# 5-2_fpga_config.net
KiCad netlist of a schematic drawn in Altium Designer
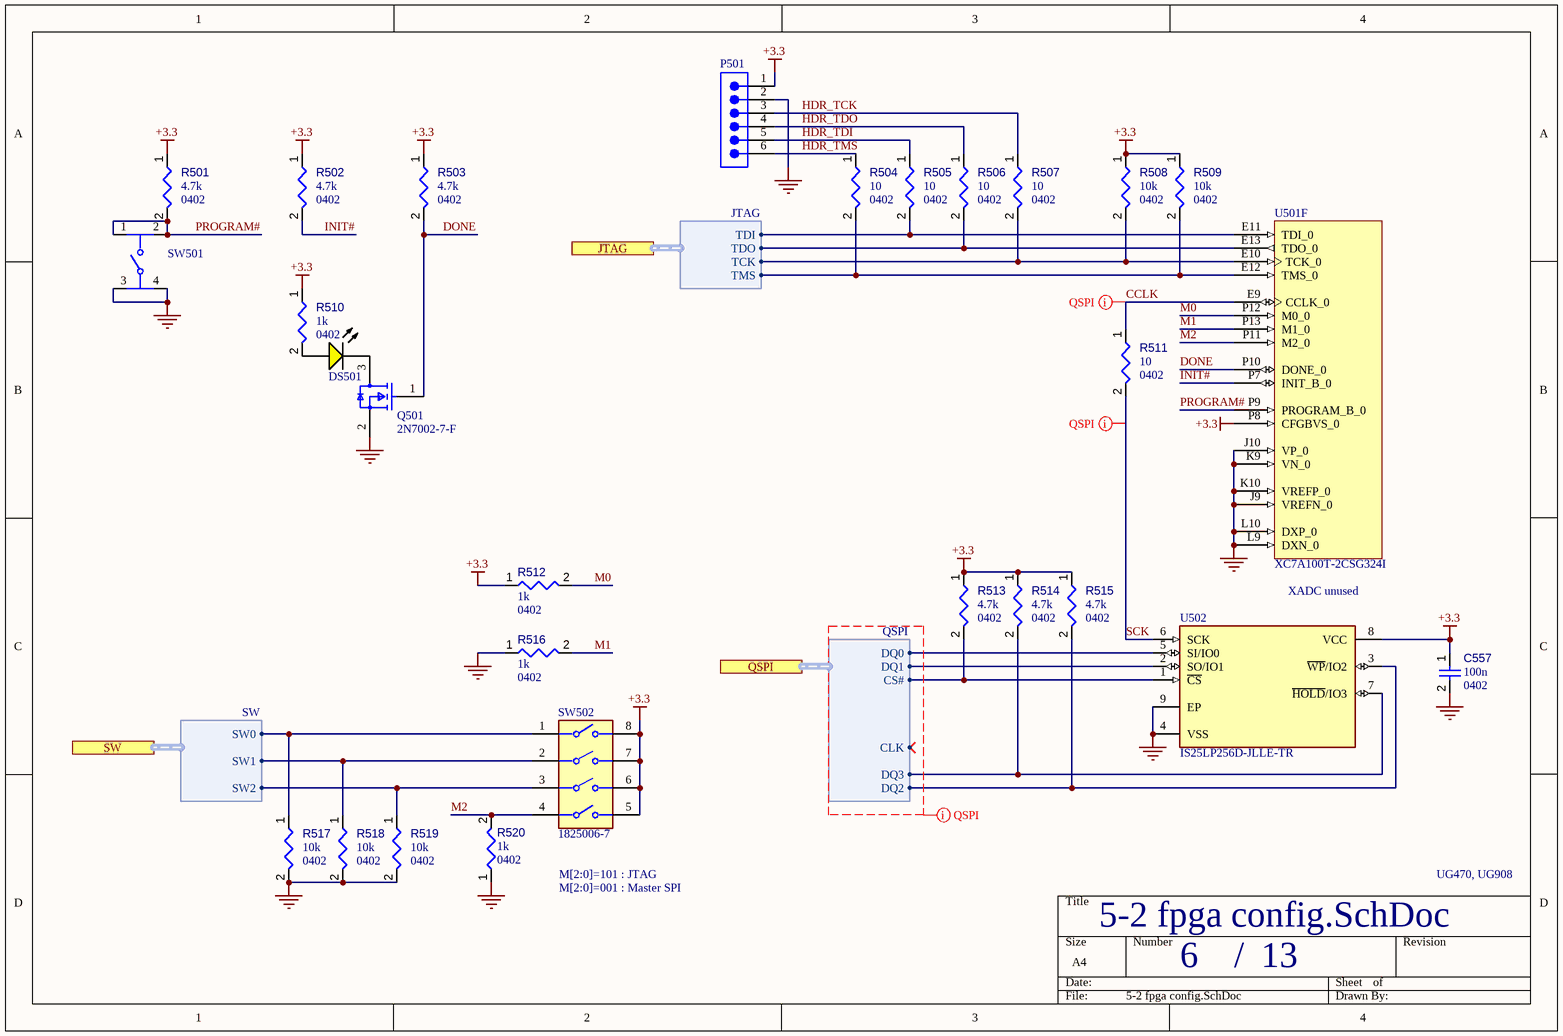
[diagram p0: 5-2 fpga config.SchDoc]

(export (version "E")
  (design (tool "Eeschema 10.0.6"))
  (components
    (comp (ref "C557")
      (value "100n")
      (footprint "CAPC0402(1005)60_L")
      (description "Capacitor")
      (fields (field (name "CASE/PACKAGE") "0402") (field (name "Comment") "Capacitors,0402,100n,16"))
      (libsource (lib "UBC Uncrewed Aircraft Systems") (part "CAP-NP-2"))
    )
    (comp (ref "DS501")
      (value "SML-LX0603YW-TR")
      (footprint "LUMX-SML-LX0603_V")
      (fields (field (name "MANUFACTURER") "Lumex"))
      (libsource (lib "Altium Content Vault") (part "LED-YELLOW-AK-2"))
    )
    (comp (ref "P501")
      (value "TSW-106-07-F-S")
      (footprint "SMTC-TSW-106-07-X-S")
      (description "0.025\" SQ Post Header, Through-hole, Vertical, -55 to 125 degC, 2.54 mm Pitch, 6-Pin, Male, RoHS")
      (fields (field (name "MANUFACTURER") "Samtec"))
      (libsource (lib "Altium Content Vault") (part "SMTC-TSW-106-X-X-S-X"))
    )
    (comp (ref "Q501")
      (value "2N7002-7-F")
      (footprint "FP-SOT23-MFG")
      (description "MOSFET N-CH 60V 115MA SOT23-3")
      (fields (field (name "VOLTAGE") "60V"))
      (libsource (lib "Altium Content Vault") (part "3b9c635fedb024a5347a57b145af9cc"))
    )
    (comp (ref "R501")
      (value "4.7k")
      (footprint "RESC0402(1005)_L")
      (description "Resistor")
      (fields (field (name "CASE/PACKAGE") "0402") (field (name "Comment") "Resistors,0402,4.7k"))
      (libsource (lib "UBC Uncrewed Aircraft Systems") (part "RES-2"))
    )
    (comp (ref "R502")
      (value "4.7k")
      (footprint "RESC0402(1005)_L")
      (description "Resistor")
      (fields (field (name "CASE/PACKAGE") "0402") (field (name "Comment") "Resistors,0402,4.7k"))
      (libsource (lib "UBC Uncrewed Aircraft Systems") (part "RES-2"))
    )
    (comp (ref "R503")
      (value "4.7k")
      (footprint "RESC0402(1005)_L")
      (description "Resistor")
      (fields (field (name "CASE/PACKAGE") "0402") (field (name "Comment") "Resistors,0402,4.7k"))
      (libsource (lib "UBC Uncrewed Aircraft Systems") (part "RES-2"))
    )
    (comp (ref "R504")
      (value "10")
      (footprint "RESC0402(1005)_L")
      (description "Resistor")
      (fields (field (name "CASE/PACKAGE") "0402") (field (name "Comment") "Resistors,0402,10"))
      (libsource (lib "UBC Uncrewed Aircraft Systems") (part "RES-2"))
    )
    (comp (ref "R505")
      (value "10")
      (footprint "RESC0402(1005)_L")
      (description "Resistor")
      (fields (field (name "CASE/PACKAGE") "0402") (field (name "Comment") "Resistors,0402,10"))
      (libsource (lib "UBC Uncrewed Aircraft Systems") (part "RES-2"))
    )
    (comp (ref "R506")
      (value "10")
      (footprint "RESC0402(1005)_L")
      (description "Resistor")
      (fields (field (name "CASE/PACKAGE") "0402") (field (name "Comment") "Resistors,0402,10"))
      (libsource (lib "UBC Uncrewed Aircraft Systems") (part "RES-2"))
    )
    (comp (ref "R507")
      (value "10")
      (footprint "RESC0402(1005)_L")
      (description "Resistor")
      (fields (field (name "CASE/PACKAGE") "0402") (field (name "Comment") "Resistors,0402,10"))
      (libsource (lib "UBC Uncrewed Aircraft Systems") (part "RES-2"))
    )
    (comp (ref "R508")
      (value "10k")
      (footprint "RESC0402(1005)_L")
      (description "Resistor")
      (fields (field (name "CASE/PACKAGE") "0402") (field (name "Comment") "Resistors,0402,10k"))
      (libsource (lib "UBC Uncrewed Aircraft Systems") (part "RES-2"))
    )
    (comp (ref "R509")
      (value "10k")
      (footprint "RESC0402(1005)_L")
      (description "Resistor")
      (fields (field (name "CASE/PACKAGE") "0402") (field (name "Comment") "Resistors,0402,10k"))
      (libsource (lib "UBC Uncrewed Aircraft Systems") (part "RES-2"))
    )
    (comp (ref "R510")
      (value "1k")
      (footprint "RESC0402(1005)_L")
      (description "Resistor")
      (fields (field (name "CASE/PACKAGE") "0402") (field (name "Comment") "Resistors,0402,1k"))
      (libsource (lib "UBC Uncrewed Aircraft Systems") (part "RES-2"))
    )
    (comp (ref "R511")
      (value "10")
      (footprint "RESC0402(1005)_L")
      (description "Resistor")
      (fields (field (name "CASE/PACKAGE") "0402") (field (name "Comment") "Resistors,0402,10"))
      (libsource (lib "UBC Uncrewed Aircraft Systems") (part "RES-2"))
    )
    (comp (ref "R512")
      (value "1k")
      (footprint "RESC0402(1005)_L")
      (description "Resistor")
      (fields (field (name "CASE/PACKAGE") "0402") (field (name "Comment") "Resistors,0402,1k"))
      (libsource (lib "UBC Uncrewed Aircraft Systems") (part "RES-2"))
    )
    (comp (ref "R513")
      (value "4.7k")
      (footprint "RESC0402(1005)_L")
      (description "Resistor")
      (fields (field (name "CASE/PACKAGE") "0402") (field (name "Comment") "Resistors,0402,4.7k"))
      (libsource (lib "UBC Uncrewed Aircraft Systems") (part "RES-2"))
    )
    (comp (ref "R514")
      (value "4.7k")
      (footprint "RESC0402(1005)_L")
      (description "Resistor")
      (fields (field (name "CASE/PACKAGE") "0402") (field (name "Comment") "Resistors,0402,4.7k"))
      (libsource (lib "UBC Uncrewed Aircraft Systems") (part "RES-2"))
    )
    (comp (ref "R515")
      (value "4.7k")
      (footprint "RESC0402(1005)_L")
      (description "Resistor")
      (fields (field (name "CASE/PACKAGE") "0402") (field (name "Comment") "Resistors,0402,4.7k"))
      (libsource (lib "UBC Uncrewed Aircraft Systems") (part "RES-2"))
    )
    (comp (ref "R516")
      (value "1k")
      (footprint "RESC0402(1005)_L")
      (description "Resistor")
      (fields (field (name "CASE/PACKAGE") "0402") (field (name "Comment") "Resistors,0402,1k"))
      (libsource (lib "UBC Uncrewed Aircraft Systems") (part "RES-2"))
    )
    (comp (ref "R517")
      (value "10k")
      (footprint "RESC0402(1005)_L")
      (description "Resistor")
      (fields (field (name "CASE/PACKAGE") "0402") (field (name "Comment") "Resistors,0402,10k"))
      (libsource (lib "UBC Uncrewed Aircraft Systems") (part "RES-2"))
    )
    (comp (ref "R518")
      (value "10k")
      (footprint "RESC0402(1005)_L")
      (description "Resistor")
      (fields (field (name "CASE/PACKAGE") "0402") (field (name "Comment") "Resistors,0402,10k"))
      (libsource (lib "UBC Uncrewed Aircraft Systems") (part "RES-2"))
    )
    (comp (ref "R519")
      (value "10k")
      (footprint "RESC0402(1005)_L")
      (description "Resistor")
      (fields (field (name "CASE/PACKAGE") "0402") (field (name "Comment") "Resistors,0402,10k"))
      (libsource (lib "UBC Uncrewed Aircraft Systems") (part "RES-2"))
    )
    (comp (ref "R520")
      (value "1k")
      (footprint "RESC0402(1005)_L")
      (description "Resistor")
      (fields (field (name "CASE/PACKAGE") "0402") (field (name "Comment") "Resistors,0402,1k"))
      (libsource (lib "UBC Uncrewed Aircraft Systems") (part "RES-2"))
    )
    (comp (ref "SW501")
      (value "PTS810SJM250SMTRLFS")
      (footprint "FP-PTS810SJM250SMTRLFS-MFG")
      (description "SWITCH TACTILE SPST-NO 0.05A 16V")
      (libsource (lib "Altium Content Vault") (part "1adf0dd01260c80cf25a44bfd6b99ba"))
    )
    (comp (ref "SW502")
      (value "1825006-7")
      (footprint "FP-1825006-7-MFG")
      (description "SWITCH SLIDE DIP SPST 25MA 24V")
      (libsource (lib "Altium Content Vault") (part "68455c0d9ce67c59adf7292e62b4e22"))
    )
    (comp (ref "U501")
      (value "XC7A100T-2CSG324I")
      (footprint "CSG324")
      (description "Artix-7 FPGA, 210 User I/Os, 0 GTP, 324-Ball BGA, Speed Grade 2, Extended Grade, Pb-Free")
      (fields (field (name "MANUFACTURER") "Xilinx") (field (name "GENERIC PART NUMBER") "XC7A100T"))
      (libsource (lib "Altium Content Vault") (part "XNLX-XC7A100T-XNLX-CSG324"))
    )
    (comp (ref "U502")
      (value "IS25LP256D-JLLE-TR")
      (footprint "FP-PG-WSON-8-IPC_A")
      (description "S25FL256SAGNFV000 128 Mbit (16 Mbyte)/256 Mbit (32 Mbyte) 3.0V SPI Flash Memory")
      (libsource (lib "Altium Content Vault") (part "248553bbdf33aab5cdb7ae52e9f9a5b"))
    )
  )
  (nets
    (net (code "4") (name "+3.3") (class "Default")
      (node (ref "C557") (pin "1") (pinfunction "1_1") (pintype "passive"))
      (node (ref "P501") (pin "1") (pinfunction "1_1") (pintype "passive"))
      (node (ref "R501") (pin "1") (pinfunction "1_1") (pintype "passive"))
      (node (ref "R502") (pin "1") (pinfunction "1_1") (pintype "passive"))
      (node (ref "R503") (pin "1") (pinfunction "1_1") (pintype "passive"))
      (node (ref "R508") (pin "1") (pinfunction "1_1") (pintype "passive"))
      (node (ref "R509") (pin "1") (pinfunction "1_1") (pintype "passive"))
      (node (ref "R510") (pin "1") (pinfunction "1_1") (pintype "passive"))
      (node (ref "R512") (pin "1") (pinfunction "1_1") (pintype "passive"))
      (node (ref "R513") (pin "1") (pinfunction "1_1") (pintype "passive"))
      (node (ref "R514") (pin "1") (pinfunction "1_1") (pintype "passive"))
      (node (ref "R515") (pin "1") (pinfunction "1_1") (pintype "passive"))
      (node (ref "SW502") (pin "5") (pinfunction "5_5") (pintype "passive"))
      (node (ref "SW502") (pin "6") (pinfunction "6_6") (pintype "passive"))
      (node (ref "SW502") (pin "7") (pinfunction "7_7") (pintype "passive"))
      (node (ref "SW502") (pin "8") (pinfunction "8_8") (pintype "passive"))
      (node (ref "U501") (pin "P8") (pinfunction "CFGBVS_0_P8") (pintype "input"))
      (node (ref "U502") (pin "8") (pinfunction "VCC_8") (pintype "power_in"))
    )
    (net (code "5") (name "/CCLK") (class "Default")
      (node (ref "R511") (pin "1") (pinfunction "1_1") (pintype "passive"))
      (node (ref "U501") (pin "E9") (pinfunction "CCLK_0_E9") (pintype "bidirectional"))
    )
    (net (code "6") (name "/CS#") (class "Default")
      (node (ref "R513") (pin "2") (pinfunction "2_2") (pintype "passive"))
      (node (ref "U502") (pin "1") (pinfunction "~{CS}_1") (pintype "input"))
    )
    (net (code "7") (name "/DONE") (class "Default")
      (node (ref "Q501") (pin "1") (pinfunction "G_1") (pintype "passive"))
      (node (ref "R503") (pin "2") (pinfunction "2_2") (pintype "passive"))
      (node (ref "U501") (pin "P10") (pinfunction "DONE_0_P10") (pintype "bidirectional"))
    )
    (net (code "8") (name "/DQ0") (class "Default")
      (node (ref "U502") (pin "5") (pinfunction "SI/IO0_5") (pintype "bidirectional"))
    )
    (net (code "9") (name "/DQ1") (class "Default")
      (node (ref "U502") (pin "2") (pinfunction "SO/IO1_2") (pintype "bidirectional"))
    )
    (net (code "10") (name "/DQ2") (class "Default")
      (node (ref "R515") (pin "2") (pinfunction "2_2") (pintype "passive"))
      (node (ref "U502") (pin "3") (pinfunction "~{WP}/IO2_3") (pintype "bidirectional"))
    )
    (net (code "11") (name "/DQ3") (class "Default")
      (node (ref "R514") (pin "2") (pinfunction "2_2") (pintype "passive"))
      (node (ref "U502") (pin "7") (pinfunction "~{HOLD}/IO3_7") (pintype "bidirectional"))
    )
    (net (code "12") (name "/HDR_TCK") (class "Default")
      (node (ref "P501") (pin "3") (pinfunction "3_3") (pintype "passive"))
      (node (ref "R507") (pin "1") (pinfunction "1_1") (pintype "passive"))
    )
    (net (code "13") (name "/HDR_TDI") (class "Default")
      (node (ref "P501") (pin "5") (pinfunction "5_5") (pintype "passive"))
      (node (ref "R505") (pin "1") (pinfunction "1_1") (pintype "passive"))
    )
    (net (code "14") (name "/HDR_TDO") (class "Default")
      (node (ref "P501") (pin "4") (pinfunction "4_4") (pintype "passive"))
      (node (ref "R506") (pin "1") (pinfunction "1_1") (pintype "passive"))
    )
    (net (code "15") (name "/HDR_TMS") (class "Default")
      (node (ref "P501") (pin "6") (pinfunction "6_6") (pintype "passive"))
      (node (ref "R504") (pin "1") (pinfunction "1_1") (pintype "passive"))
    )
    (net (code "16") (name "/INIT#") (class "Default")
      (node (ref "R502") (pin "2") (pinfunction "2_2") (pintype "passive"))
      (node (ref "U501") (pin "P7") (pinfunction "INIT_B_0_P7") (pintype "bidirectional"))
    )
    (net (code "17") (name "/M0") (class "Default")
      (node (ref "R512") (pin "2") (pinfunction "2_2") (pintype "passive"))
      (node (ref "U501") (pin "P12") (pinfunction "M0_0_P12") (pintype "input"))
    )
    (net (code "18") (name "/M1") (class "Default")
      (node (ref "R516") (pin "2") (pinfunction "2_2") (pintype "passive"))
      (node (ref "U501") (pin "P13") (pinfunction "M1_0_P13") (pintype "input"))
    )
    (net (code "19") (name "/M2") (class "Default")
      (node (ref "R520") (pin "2") (pinfunction "2_2") (pintype "passive"))
      (node (ref "SW502") (pin "4") (pinfunction "4_4") (pintype "passive"))
      (node (ref "U501") (pin "P11") (pinfunction "M2_0_P11") (pintype "input"))
    )
    (net (code "20") (name "/PROGRAM#") (class "Default")
      (node (ref "R501") (pin "2") (pinfunction "2_2") (pintype "passive"))
      (node (ref "SW501") (pin "1") (pinfunction "1_1") (pintype "passive"))
      (node (ref "SW501") (pin "2") (pinfunction "2_2") (pintype "passive"))
      (node (ref "U501") (pin "P9") (pinfunction "PROGRAM_B_0_P9") (pintype "input"))
    )
    (net (code "21") (name "/SCK") (class "Default")
      (node (ref "R511") (pin "2") (pinfunction "2_2") (pintype "passive"))
      (node (ref "U502") (pin "6") (pinfunction "SCK_6") (pintype "input"))
    )
    (net (code "22") (name "/SW0") (class "Default")
      (node (ref "R517") (pin "1") (pinfunction "1_1") (pintype "passive"))
      (node (ref "SW502") (pin "1") (pinfunction "1_1") (pintype "passive"))
    )
    (net (code "23") (name "/SW1") (class "Default")
      (node (ref "R518") (pin "1") (pinfunction "1_1") (pintype "passive"))
      (node (ref "SW502") (pin "2") (pinfunction "2_2") (pintype "passive"))
    )
    (net (code "24") (name "/SW2") (class "Default")
      (node (ref "R519") (pin "1") (pinfunction "1_1") (pintype "passive"))
      (node (ref "SW502") (pin "3") (pinfunction "3_3") (pintype "passive"))
    )
    (net (code "25") (name "/TCK") (class "Default")
      (node (ref "R507") (pin "2") (pinfunction "2_2") (pintype "passive"))
      (node (ref "R508") (pin "2") (pinfunction "2_2") (pintype "passive"))
      (node (ref "U501") (pin "E10") (pinfunction "TCK_0_E10") (pintype "input"))
    )
    (net (code "26") (name "/TDI") (class "Default")
      (node (ref "R505") (pin "2") (pinfunction "2_2") (pintype "passive"))
      (node (ref "U501") (pin "E11") (pinfunction "TDI_0_E11") (pintype "input"))
    )
    (net (code "27") (name "/TDO") (class "Default")
      (node (ref "R506") (pin "2") (pinfunction "2_2") (pintype "passive"))
      (node (ref "U501") (pin "E13") (pinfunction "TDO_0_E13") (pintype "output"))
    )
    (net (code "28") (name "/TMS") (class "Default")
      (node (ref "R504") (pin "2") (pinfunction "2_2") (pintype "passive"))
      (node (ref "R509") (pin "2") (pinfunction "2_2") (pintype "passive"))
      (node (ref "U501") (pin "E12") (pinfunction "TMS_0_E12") (pintype "input"))
    )
    (net (code "32") (name "GND") (class "Default")
      (node (ref "C557") (pin "2") (pinfunction "2_2") (pintype "passive"))
      (node (ref "P501") (pin "2") (pinfunction "2_2") (pintype "passive"))
      (node (ref "Q501") (pin "2") (pinfunction "S_2") (pintype "passive"))
      (node (ref "R516") (pin "1") (pinfunction "1_1") (pintype "passive"))
      (node (ref "R517") (pin "2") (pinfunction "2_2") (pintype "passive"))
      (node (ref "R518") (pin "2") (pinfunction "2_2") (pintype "passive"))
      (node (ref "R519") (pin "2") (pinfunction "2_2") (pintype "passive"))
      (node (ref "R520") (pin "1") (pinfunction "1_1") (pintype "passive"))
      (node (ref "SW501") (pin "3") (pinfunction "3_3") (pintype "passive"))
      (node (ref "SW501") (pin "4") (pinfunction "4_4") (pintype "passive"))
      (node (ref "U501") (pin "J10") (pinfunction "VP_0_J10") (pintype "input"))
      (node (ref "U501") (pin "J9") (pinfunction "VREFN_0_J9") (pintype "input"))
      (node (ref "U501") (pin "K10") (pinfunction "VREFP_0_K10") (pintype "input"))
      (node (ref "U501") (pin "K9") (pinfunction "VN_0_K9") (pintype "input"))
      (node (ref "U501") (pin "L10") (pinfunction "DXP_0_L10") (pintype "input"))
      (node (ref "U501") (pin "L9") (pinfunction "DXN_0_L9") (pintype "input"))
      (node (ref "U502") (pin "4") (pinfunction "VSS_4") (pintype "power_in"))
      (node (ref "U502") (pin "9") (pinfunction "EP_9") (pintype "passive"))
    )
    (net (code "33") (name "Net-(DS501-A)") (class "Default")
      (node (ref "DS501") (pin "1") (pinfunction "A_1") (pintype "passive"))
      (node (ref "R510") (pin "2") (pinfunction "2_2") (pintype "passive"))
    )
    (net (code "34") (name "Net-(DS501-K)") (class "Default")
      (node (ref "DS501") (pin "2") (pinfunction "K_2") (pintype "passive"))
      (node (ref "Q501") (pin "3") (pinfunction "D_3") (pintype "passive"))
    )
  )
)
